# main.net
KiCad netlist of a schematic drawn in Altium Designer
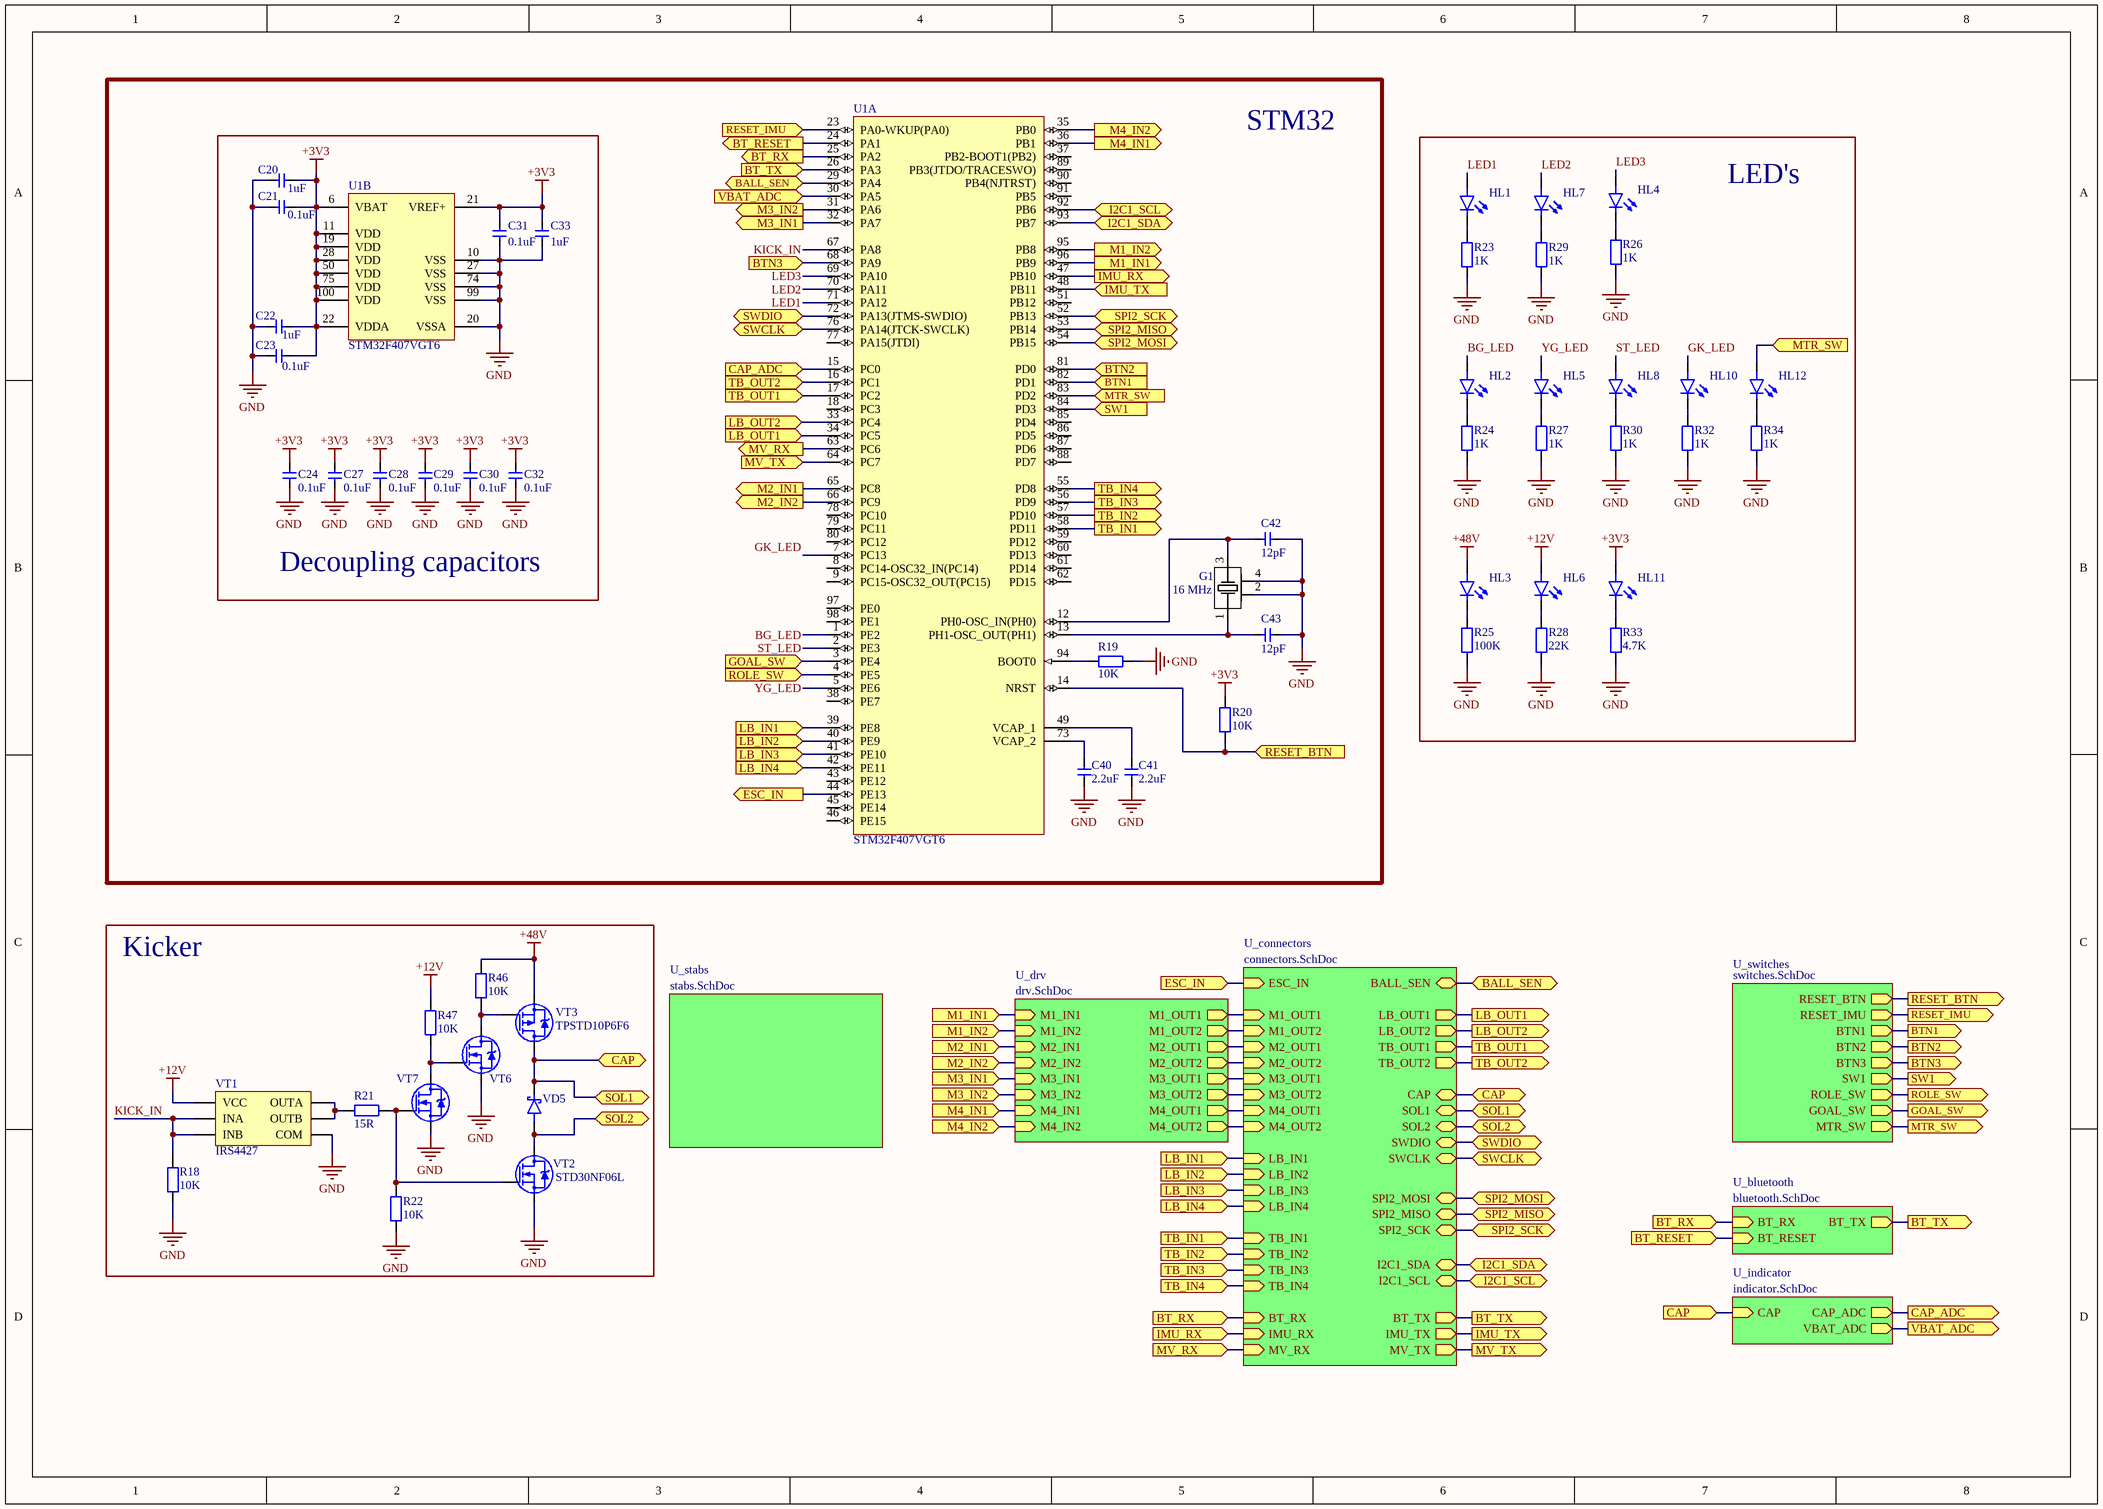
[diagram p0: main.SchDoc]

(export (version "E")
  (design (tool "Eeschema 10.0.6"))
  (components
    (comp (ref "C20")
      (value "1uF")
      (footprint "CAP0805")
      (description "Ceramic SMD Cap")
      (libsource (lib "Asterisk") (part "CAP Ceramic"))
    )
    (comp (ref "C21")
      (value "0.1uF")
      (footprint "CAP0805")
      (description "Ceramic SMD Cap")
      (libsource (lib "Asterisk") (part "CAP Ceramic"))
    )
    (comp (ref "C22")
      (value "1uF")
      (footprint "CAP0805")
      (description "Ceramic SMD Cap")
      (libsource (lib "Asterisk") (part "CAP Ceramic"))
    )
    (comp (ref "C23")
      (value "0.1uF")
      (footprint "CAP0805")
      (description "Ceramic SMD Cap")
      (libsource (lib "Asterisk") (part "CAP Ceramic"))
    )
    (comp (ref "C24")
      (value "0.1uF")
      (footprint "CAP0805")
      (description "Ceramic SMD Cap")
      (libsource (lib "Asterisk") (part "CAP Ceramic"))
    )
    (comp (ref "C27")
      (value "0.1uF")
      (footprint "CAP0805")
      (description "Ceramic SMD Cap")
      (libsource (lib "Asterisk") (part "CAP Ceramic"))
    )
    (comp (ref "C28")
      (value "0.1uF")
      (footprint "CAP0805")
      (description "Ceramic SMD Cap")
      (libsource (lib "Asterisk") (part "CAP Ceramic"))
    )
    (comp (ref "C29")
      (value "0.1uF")
      (footprint "CAP0805")
      (description "Ceramic SMD Cap")
      (libsource (lib "Asterisk") (part "CAP Ceramic"))
    )
    (comp (ref "C30")
      (value "0.1uF")
      (footprint "CAP0805")
      (description "Ceramic SMD Cap")
      (libsource (lib "Asterisk") (part "CAP Ceramic"))
    )
    (comp (ref "C31")
      (value "0.1uF")
      (footprint "CAP0805")
      (description "Ceramic SMD Cap")
      (libsource (lib "Asterisk") (part "CAP Ceramic"))
    )
    (comp (ref "C32")
      (value "0.1uF")
      (footprint "CAP0805")
      (description "Ceramic SMD Cap")
      (libsource (lib "Asterisk") (part "CAP Ceramic"))
    )
    (comp (ref "C33")
      (value "1uF")
      (footprint "CAP0805")
      (description "Ceramic SMD Cap")
      (libsource (lib "Asterisk") (part "CAP Ceramic"))
    )
    (comp (ref "C40")
      (value "2.2uF")
      (footprint "CAP0805")
      (description "Ceramic SMD Cap")
      (libsource (lib "") (part "CAP Ceramic_1"))
    )
    (comp (ref "C41")
      (value "2.2uF")
      (footprint "CAP0805")
      (description "Ceramic SMD Cap")
      (libsource (lib "") (part "CAP Ceramic_1"))
    )
    (comp (ref "C42")
      (value "12pF")
      (footprint "CAP0805")
      (description "Ceramic SMD Cap")
      (libsource (lib "Asterisk") (part "CAP Ceramic"))
    )
    (comp (ref "C43")
      (value "12pF")
      (footprint "CAP0805")
      (description "Ceramic SMD Cap")
      (libsource (lib "Asterisk") (part "CAP Ceramic"))
    )
    (comp (ref "G1")
      (value "16 MHz")
      (footprint "TSX-3225")
      (description "quartz 16MHz")
      (fields
        (field (name "PART NUMBER") "TSX-3225 24.0000MF15X-AC6")
        (field (name "DIGI-KEY PART NUMBER") "SER4180CT-ND")
      )
      (libsource (lib "SssAccesDatbase") (part "CTX957CT"))
    )
    (comp (ref "HL1")
      (value "White")
      (footprint "LED0603_WHITE")
      (description "LED1")
      (libsource (lib "Asterisk") (part "LED"))
    )
    (comp (ref "HL2")
      (value "White")
      (footprint "LED0603_WHITE")
      (description "BG")
      (libsource (lib "Asterisk") (part "LED"))
    )
    (comp (ref "HL3")
      (value "Green")
      (footprint "LED0603_GREEN")
      (description "48V power")
      (libsource (lib "Asterisk") (part "LED"))
    )
    (comp (ref "HL4")
      (value "White")
      (footprint "LED0603_WHITE")
      (description "LED3")
      (libsource (lib "Asterisk") (part "LED"))
    )
    (comp (ref "HL5")
      (value "White")
      (footprint "LED0603_WHITE")
      (description "YG")
      (libsource (lib "Asterisk") (part "LED"))
    )
    (comp (ref "HL6")
      (value "Green")
      (footprint "LED0603_GREEN")
      (description "12V power")
      (libsource (lib "Asterisk") (part "LED"))
    )
    (comp (ref "HL7")
      (value "White")
      (footprint "LED0603_WHITE")
      (description "LED2")
      (libsource (lib "Asterisk") (part "LED"))
    )
    (comp (ref "HL8")
      (value "White")
      (footprint "LED0603_WHITE")
      (description "ST")
      (libsource (lib "Asterisk") (part "LED"))
    )
    (comp (ref "HL10")
      (value "White")
      (footprint "LED0603_WHITE")
      (description "GK")
      (libsource (lib "Asterisk") (part "LED"))
    )
    (comp (ref "HL11")
      (value "Green")
      (footprint "LED0603_GREEN")
      (description "3V3 power")
      (libsource (lib "Asterisk") (part "LED"))
    )
    (comp (ref "HL12")
      (value "Red")
      (footprint "LED0603_RED")
      (description "M_ON")
      (libsource (lib "Asterisk") (part "LED"))
    )
    (comp (ref "R18")
      (value "10K")
      (footprint "RES0805")
      (description "RES smd")
      (libsource (lib "Asterisk") (part "RES"))
    )
    (comp (ref "R19")
      (value "10K")
      (footprint "RES0805")
      (description "RES smd")
      (libsource (lib "Asterisk") (part "RES"))
    )
    (comp (ref "R20")
      (value "10K")
      (footprint "RES0805")
      (description "RES smd")
      (libsource (lib "Asterisk") (part "RES"))
    )
    (comp (ref "R21")
      (value "15R")
      (footprint "RES1206")
      (description "RES smd")
      (libsource (lib "Asterisk") (part "RES"))
    )
    (comp (ref "R22")
      (value "10K")
      (footprint "RES0805")
      (description "RES smd")
      (libsource (lib "Asterisk") (part "RES"))
    )
    (comp (ref "R23")
      (value "1K")
      (footprint "RES0805")
      (description "RES smd")
      (libsource (lib "Asterisk") (part "RES"))
    )
    (comp (ref "R24")
      (value "1K")
      (footprint "RES0805")
      (description "RES smd")
      (libsource (lib "Asterisk") (part "RES"))
    )
    (comp (ref "R25")
      (value "100K")
      (footprint "RES0805")
      (description "RES smd")
      (libsource (lib "Asterisk") (part "RES"))
    )
    (comp (ref "R26")
      (value "1K")
      (footprint "RES0805")
      (description "RES smd")
      (libsource (lib "Asterisk") (part "RES"))
    )
    (comp (ref "R27")
      (value "1K")
      (footprint "RES0805")
      (description "RES smd")
      (libsource (lib "Asterisk") (part "RES"))
    )
    (comp (ref "R28")
      (value "22K")
      (footprint "RES0805")
      (description "RES smd")
      (libsource (lib "Asterisk") (part "RES"))
    )
    (comp (ref "R29")
      (value "1K")
      (footprint "RES0805")
      (description "RES smd")
      (libsource (lib "Asterisk") (part "RES"))
    )
    (comp (ref "R30")
      (value "1K")
      (footprint "RES0805")
      (description "RES smd")
      (libsource (lib "Asterisk") (part "RES"))
    )
    (comp (ref "R32")
      (value "1K")
      (footprint "RES0805")
      (description "RES smd")
      (libsource (lib "Asterisk") (part "RES"))
    )
    (comp (ref "R33")
      (value "4.7K")
      (footprint "RES0805")
      (description "RES smd")
      (libsource (lib "Asterisk") (part "RES"))
    )
    (comp (ref "R34")
      (value "1K")
      (footprint "RES0805")
      (description "RES smd")
      (libsource (lib "Asterisk") (part "RES"))
    )
    (comp (ref "R46")
      (value "10K")
      (footprint "RES0805")
      (description "RES smd")
      (libsource (lib "Asterisk") (part "RES"))
    )
    (comp (ref "R47")
      (value "10K")
      (footprint "RES0805")
      (description "RES smd")
      (libsource (lib "Asterisk") (part "RES"))
    )
    (comp (ref "U1")
      (value "STM32F407VGT6")
      (footprint "LQFP100")
      (fields (field (name "MANUFACTURER") "STMicroelectronics"))
      (libsource (lib "") (part "STM32F407VGT6_1"))
    )
    (comp (ref "VD5")
      (value "~")
      (footprint "DO-214AC (SMA)")
      (description "Diode Schottky")
      (libsource (lib "Asterisk") (part "Diode Schottky"))
    )
    (comp (ref "VT1")
      (value "IRS4427")
      (footprint "SOIC-8")
      (description "Mosfet driver")
      (libsource (lib "Asterisk") (part "IRS4427"))
    )
    (comp (ref "VT2")
      (value "STD30NF06L")
      (footprint "DPAK")
      (description "N-MOSFET\r\nUds = 60 V\r\nIds = 30 A\r\nRds = 0.023 Ohm\r\nP = 55 W")
      (libsource (lib "Asterisk") (part "STD30NF06L"))
    )
    (comp (ref "VT3")
      (value "TPSTD10P6F6")
      (footprint "DPAK")
      (description "P-MOSFET\r\nUds = 60 V\r\nIds = 13 A\r\nRds = 0.100 Ohm\r\nP = 60 W")
      (libsource (lib "Asterisk") (part "TPSTD10P6F6"))
    )
    (comp (ref "VT6")
      (value "IRLML2502")
      (footprint "SOT-23-3")
      (description "N-MOSFET\r\nUds = 20 V\r\nIds = 4.2 A\r\nRds = 0.035 Ohm\r\nP = 1,25 W")
      (libsource (lib "Asterisk") (part "IRLML2502"))
    )
    (comp (ref "VT7")
      (value "IRLML2502")
      (footprint "SOT-23-3")
      (description "N-MOSFET\r\nUds = 20 V\r\nIds = 4.2 A\r\nRds = 0.035 Ohm\r\nP = 8 W")
      (libsource (lib "Asterisk") (part "IRLML2502"))
    )
  )
  (nets
    (net (code "1") (name "+3V3") (class "Default")
      (node (ref "C20") (pin "1") (pinfunction "1_1") (pintype "passive"))
      (node (ref "C21") (pin "1") (pinfunction "1_1") (pintype "passive"))
      (node (ref "C22") (pin "1") (pinfunction "1_1") (pintype "passive"))
      (node (ref "C23") (pin "1") (pinfunction "1_1") (pintype "passive"))
      (node (ref "C24") (pin "1") (pinfunction "1_1") (pintype "passive"))
      (node (ref "C27") (pin "1") (pinfunction "1_1") (pintype "passive"))
      (node (ref "C28") (pin "1") (pinfunction "1_1") (pintype "passive"))
      (node (ref "C29") (pin "1") (pinfunction "1_1") (pintype "passive"))
      (node (ref "C30") (pin "1") (pinfunction "1_1") (pintype "passive"))
      (node (ref "C31") (pin "2") (pinfunction "2_2") (pintype "passive"))
      (node (ref "C32") (pin "1") (pinfunction "1_1") (pintype "passive"))
      (node (ref "C33") (pin "2") (pinfunction "2_2") (pintype "passive"))
      (node (ref "HL11") (pin "2") (pinfunction "A_2") (pintype "passive"))
      (node (ref "R20") (pin "1") (pinfunction "1_1") (pintype "passive"))
      (node (ref "U1") (pin "100") (pinfunction "VDD_100") (pintype "power_in"))
      (node (ref "U1") (pin "11") (pinfunction "VDD_11") (pintype "power_in"))
      (node (ref "U1") (pin "19") (pinfunction "VDD_19") (pintype "power_in"))
      (node (ref "U1") (pin "21") (pinfunction "VREF+_21") (pintype "power_in"))
      (node (ref "U1") (pin "22") (pinfunction "VDDA_22") (pintype "power_in"))
      (node (ref "U1") (pin "28") (pinfunction "VDD_28") (pintype "power_in"))
      (node (ref "U1") (pin "50") (pinfunction "VDD_50") (pintype "power_in"))
      (node (ref "U1") (pin "6") (pinfunction "VBAT_6") (pintype "power_in"))
      (node (ref "U1") (pin "75") (pinfunction "VDD_75") (pintype "power_in"))
    )
    (net (code "2") (name "+12V") (class "Default")
      (node (ref "HL6") (pin "2") (pinfunction "A_2") (pintype "passive"))
      (node (ref "R47") (pin "2") (pinfunction "2_2") (pintype "passive"))
      (node (ref "VT1") (pin "6") (pinfunction "VCC_6") (pintype "passive"))
    )
    (net (code "3") (name "+48V") (class "Default")
      (node (ref "HL3") (pin "2") (pinfunction "A_2") (pintype "passive"))
      (node (ref "R46") (pin "2") (pinfunction "2_2") (pintype "passive"))
      (node (ref "VT3") (pin "S") (pinfunction "S_S") (pintype "passive"))
    )
    (net (code "4") (name "/BALL_SEN") (class "Default")
      (node (ref "U1") (pin "29") (pinfunction "PA4_29") (pintype "bidirectional"))
    )
    (net (code "5") (name "/BG_LED") (class "Default")
      (node (ref "HL2") (pin "2") (pinfunction "A_2") (pintype "passive"))
      (node (ref "U1") (pin "1") (pinfunction "PE2_1") (pintype "bidirectional"))
    )
    (net (code "6") (name "/BTN1") (class "Default")
      (node (ref "U1") (pin "82") (pinfunction "PD1_82") (pintype "bidirectional"))
    )
    (net (code "7") (name "/BTN2") (class "Default")
      (node (ref "U1") (pin "81") (pinfunction "PD0_81") (pintype "bidirectional"))
    )
    (net (code "8") (name "/BTN3") (class "Default")
      (node (ref "U1") (pin "68") (pinfunction "PA9_68") (pintype "bidirectional"))
    )
    (net (code "9") (name "/BT_RESET") (class "Default")
      (node (ref "U1") (pin "24") (pinfunction "PA1_24") (pintype "bidirectional"))
    )
    (net (code "10") (name "/BT_RX") (class "Default")
      (node (ref "U1") (pin "25") (pinfunction "PA2_25") (pintype "bidirectional"))
    )
    (net (code "11") (name "/BT_TX") (class "Default")
      (node (ref "U1") (pin "26") (pinfunction "PA3_26") (pintype "bidirectional"))
    )
    (net (code "12") (name "/CAP") (class "Default")
      (node (ref "VD5") (pin "K") (pinfunction "K_K") (pintype "passive"))
      (node (ref "VT3") (pin "D") (pinfunction "D_D") (pintype "passive"))
    )
    (net (code "13") (name "/CAP_ADC") (class "Default")
      (node (ref "U1") (pin "15") (pinfunction "PC0_15") (pintype "bidirectional"))
    )
    (net (code "14") (name "/ESC_IN") (class "Default")
      (node (ref "U1") (pin "44") (pinfunction "PE13_44") (pintype "bidirectional"))
    )
    (net (code "15") (name "/GK_LED") (class "Default")
      (node (ref "HL10") (pin "2") (pinfunction "A_2") (pintype "passive"))
      (node (ref "U1") (pin "7") (pinfunction "PC13_7") (pintype "bidirectional"))
    )
    (net (code "16") (name "/GOAL_SW") (class "Default")
      (node (ref "U1") (pin "3") (pinfunction "PE4_3") (pintype "bidirectional"))
    )
    (net (code "17") (name "/I2C1_SCL") (class "Default")
      (node (ref "U1") (pin "92") (pinfunction "PB6_92") (pintype "bidirectional"))
    )
    (net (code "18") (name "/I2C1_SDA") (class "Default")
      (node (ref "U1") (pin "93") (pinfunction "PB7_93") (pintype "bidirectional"))
    )
    (net (code "19") (name "/IMU_RX") (class "Default")
      (node (ref "U1") (pin "47") (pinfunction "PB10_47") (pintype "bidirectional"))
    )
    (net (code "20") (name "/IMU_TX") (class "Default")
      (node (ref "U1") (pin "48") (pinfunction "PB11_48") (pintype "bidirectional"))
    )
    (net (code "21") (name "/KICK_IN") (class "Default")
      (node (ref "R18") (pin "2") (pinfunction "2_2") (pintype "passive"))
      (node (ref "U1") (pin "67") (pinfunction "PA8_67") (pintype "bidirectional"))
      (node (ref "VT1") (pin "2") (pinfunction "INA_2") (pintype "passive"))
      (node (ref "VT1") (pin "4") (pinfunction "INB_4") (pintype "passive"))
    )
    (net (code "22") (name "/LB_IN1") (class "Default")
      (node (ref "U1") (pin "39") (pinfunction "PE8_39") (pintype "bidirectional"))
    )
    (net (code "23") (name "/LB_IN2") (class "Default")
      (node (ref "U1") (pin "40") (pinfunction "PE9_40") (pintype "bidirectional"))
    )
    (net (code "24") (name "/LB_IN3") (class "Default")
      (node (ref "U1") (pin "41") (pinfunction "PE10_41") (pintype "bidirectional"))
    )
    (net (code "25") (name "/LB_IN4") (class "Default")
      (node (ref "U1") (pin "42") (pinfunction "PE11_42") (pintype "bidirectional"))
    )
    (net (code "26") (name "/LB_OUT1") (class "Default")
      (node (ref "U1") (pin "34") (pinfunction "PC5_34") (pintype "bidirectional"))
    )
    (net (code "27") (name "/LB_OUT2") (class "Default")
      (node (ref "U1") (pin "33") (pinfunction "PC4_33") (pintype "bidirectional"))
    )
    (net (code "28") (name "/LED1") (class "Default")
      (node (ref "HL1") (pin "2") (pinfunction "A_2") (pintype "passive"))
      (node (ref "U1") (pin "71") (pinfunction "PA12_71") (pintype "bidirectional"))
    )
    (net (code "29") (name "/LED2") (class "Default")
      (node (ref "HL7") (pin "2") (pinfunction "A_2") (pintype "passive"))
      (node (ref "U1") (pin "70") (pinfunction "PA11_70") (pintype "bidirectional"))
    )
    (net (code "30") (name "/LED3") (class "Default")
      (node (ref "HL4") (pin "2") (pinfunction "A_2") (pintype "passive"))
      (node (ref "U1") (pin "69") (pinfunction "PA10_69") (pintype "bidirectional"))
    )
    (net (code "31") (name "/M1_IN1") (class "Default")
      (node (ref "U1") (pin "96") (pinfunction "PB9_96") (pintype "bidirectional"))
    )
    (net (code "32") (name "/M1_IN2") (class "Default")
      (node (ref "U1") (pin "95") (pinfunction "PB8_95") (pintype "bidirectional"))
    )
    (net (code "35") (name "/M2_IN1") (class "Default")
      (node (ref "U1") (pin "65") (pinfunction "PC8_65") (pintype "bidirectional"))
    )
    (net (code "36") (name "/M2_IN2") (class "Default")
      (node (ref "U1") (pin "66") (pinfunction "PC9_66") (pintype "bidirectional"))
    )
    (net (code "39") (name "/M3_IN1") (class "Default")
      (node (ref "U1") (pin "32") (pinfunction "PA7_32") (pintype "bidirectional"))
    )
    (net (code "40") (name "/M3_IN2") (class "Default")
      (node (ref "U1") (pin "31") (pinfunction "PA6_31") (pintype "bidirectional"))
    )
    (net (code "43") (name "/M4_IN1") (class "Default")
      (node (ref "U1") (pin "36") (pinfunction "PB1_36") (pintype "bidirectional"))
    )
    (net (code "44") (name "/M4_IN2") (class "Default")
      (node (ref "U1") (pin "35") (pinfunction "PB0_35") (pintype "bidirectional"))
    )
    (net (code "47") (name "/MTR_SW") (class "Default")
      (node (ref "HL12") (pin "2") (pinfunction "A_2") (pintype "passive"))
      (node (ref "U1") (pin "83") (pinfunction "PD2_83") (pintype "bidirectional"))
    )
    (net (code "48") (name "/MV_RX") (class "Default")
      (node (ref "U1") (pin "63") (pinfunction "PC6_63") (pintype "bidirectional"))
    )
    (net (code "49") (name "/MV_TX") (class "Default")
      (node (ref "U1") (pin "64") (pinfunction "PC7_64") (pintype "bidirectional"))
    )
    (net (code "50") (name "/RESET_BTN") (class "Default")
      (node (ref "R20") (pin "2") (pinfunction "2_2") (pintype "passive"))
      (node (ref "U1") (pin "14") (pinfunction "NRST_14") (pintype "bidirectional"))
    )
    (net (code "51") (name "/RESET_IMU") (class "Default")
      (node (ref "U1") (pin "23") (pinfunction "PA0-WKUP(PA0)_23") (pintype "bidirectional"))
    )
    (net (code "52") (name "/ROLE_SW") (class "Default")
      (node (ref "U1") (pin "4") (pinfunction "PE5_4") (pintype "bidirectional"))
    )
    (net (code "53") (name "/SOL2") (class "Default")
      (node (ref "VD5") (pin "A") (pinfunction "A_A") (pintype "passive"))
      (node (ref "VT2") (pin "D") (pinfunction "D_D") (pintype "passive"))
    )
    (net (code "54") (name "/SPI2_MISO") (class "Default")
      (node (ref "U1") (pin "53") (pinfunction "PB14_53") (pintype "bidirectional"))
    )
    (net (code "55") (name "/SPI2_MOSI") (class "Default")
      (node (ref "U1") (pin "54") (pinfunction "PB15_54") (pintype "bidirectional"))
    )
    (net (code "56") (name "/SPI2_SCK") (class "Default")
      (node (ref "U1") (pin "52") (pinfunction "PB13_52") (pintype "bidirectional"))
    )
    (net (code "57") (name "/ST_LED") (class "Default")
      (node (ref "HL8") (pin "2") (pinfunction "A_2") (pintype "passive"))
      (node (ref "U1") (pin "2") (pinfunction "PE3_2") (pintype "bidirectional"))
    )
    (net (code "58") (name "/SW1") (class "Default")
      (node (ref "U1") (pin "84") (pinfunction "PD3_84") (pintype "bidirectional"))
    )
    (net (code "59") (name "/SWCLK") (class "Default")
      (node (ref "U1") (pin "76") (pinfunction "PA14(JTCK-SWCLK)_76") (pintype "bidirectional"))
    )
    (net (code "60") (name "/SWDIO") (class "Default")
      (node (ref "U1") (pin "72") (pinfunction "PA13(JTMS-SWDIO)_72") (pintype "bidirectional"))
    )
    (net (code "61") (name "/TB_IN1") (class "Default")
      (node (ref "U1") (pin "58") (pinfunction "PD11_58") (pintype "bidirectional"))
    )
    (net (code "62") (name "/TB_IN2") (class "Default")
      (node (ref "U1") (pin "57") (pinfunction "PD10_57") (pintype "bidirectional"))
    )
    (net (code "63") (name "/TB_IN3") (class "Default")
      (node (ref "U1") (pin "56") (pinfunction "PD9_56") (pintype "bidirectional"))
    )
    (net (code "64") (name "/TB_IN4") (class "Default")
      (node (ref "U1") (pin "55") (pinfunction "PD8_55") (pintype "bidirectional"))
    )
    (net (code "65") (name "/TB_OUT1") (class "Default")
      (node (ref "U1") (pin "17") (pinfunction "PC2_17") (pintype "bidirectional"))
    )
    (net (code "66") (name "/TB_OUT2") (class "Default")
      (node (ref "U1") (pin "16") (pinfunction "PC1_16") (pintype "bidirectional"))
    )
    (net (code "67") (name "/VBAT_ADC") (class "Default")
      (node (ref "U1") (pin "30") (pinfunction "PA5_30") (pintype "bidirectional"))
    )
    (net (code "68") (name "/YG_LED") (class "Default")
      (node (ref "HL5") (pin "2") (pinfunction "A_2") (pintype "passive"))
      (node (ref "U1") (pin "5") (pinfunction "PE6_5") (pintype "bidirectional"))
    )
    (net (code "69") (name "GND") (class "Default")
      (node (ref "C20") (pin "2") (pinfunction "2_2") (pintype "passive"))
      (node (ref "C21") (pin "2") (pinfunction "2_2") (pintype "passive"))
      (node (ref "C22") (pin "2") (pinfunction "2_2") (pintype "passive"))
      (node (ref "C23") (pin "2") (pinfunction "2_2") (pintype "passive"))
      (node (ref "C24") (pin "2") (pinfunction "2_2") (pintype "passive"))
      (node (ref "C27") (pin "2") (pinfunction "2_2") (pintype "passive"))
      (node (ref "C28") (pin "2") (pinfunction "2_2") (pintype "passive"))
      (node (ref "C29") (pin "2") (pinfunction "2_2") (pintype "passive"))
      (node (ref "C30") (pin "2") (pinfunction "2_2") (pintype "passive"))
      (node (ref "C31") (pin "1") (pinfunction "1_1") (pintype "passive"))
      (node (ref "C32") (pin "2") (pinfunction "2_2") (pintype "passive"))
      (node (ref "C33") (pin "1") (pinfunction "1_1") (pintype "passive"))
      (node (ref "C40") (pin "1") (pinfunction "1_1") (pintype "passive"))
      (node (ref "C41") (pin "1") (pinfunction "1_1") (pintype "passive"))
      (node (ref "C42") (pin "2") (pinfunction "2_2") (pintype "passive"))
      (node (ref "C43") (pin "2") (pinfunction "2_2") (pintype "passive"))
      (node (ref "G1") (pin "2") (pinfunction "2_2") (pintype "passive"))
      (node (ref "G1") (pin "4") (pinfunction "4_4") (pintype "passive"))
      (node (ref "R18") (pin "1") (pinfunction "1_1") (pintype "passive"))
      (node (ref "R19") (pin "1") (pinfunction "1_1") (pintype "passive"))
      (node (ref "R22") (pin "1") (pinfunction "1_1") (pintype "passive"))
      (node (ref "R23") (pin "1") (pinfunction "1_1") (pintype "passive"))
      (node (ref "R24") (pin "1") (pinfunction "1_1") (pintype "passive"))
      (node (ref "R25") (pin "1") (pinfunction "1_1") (pintype "passive"))
      (node (ref "R26") (pin "1") (pinfunction "1_1") (pintype "passive"))
      (node (ref "R27") (pin "1") (pinfunction "1_1") (pintype "passive"))
      (node (ref "R28") (pin "1") (pinfunction "1_1") (pintype "passive"))
      (node (ref "R29") (pin "1") (pinfunction "1_1") (pintype "passive"))
      (node (ref "R30") (pin "1") (pinfunction "1_1") (pintype "passive"))
      (node (ref "R32") (pin "1") (pinfunction "1_1") (pintype "passive"))
      (node (ref "R33") (pin "1") (pinfunction "1_1") (pintype "passive"))
      (node (ref "R34") (pin "1") (pinfunction "1_1") (pintype "passive"))
      (node (ref "U1") (pin "10") (pinfunction "VSS_10") (pintype "power_in"))
      (node (ref "U1") (pin "20") (pinfunction "VSSA_20") (pintype "power_in"))
      (node (ref "U1") (pin "27") (pinfunction "VSS_27") (pintype "power_in"))
      (node (ref "U1") (pin "74") (pinfunction "VSS_74") (pintype "power_in"))
      (node (ref "U1") (pin "99") (pinfunction "VSS_99") (pintype "power_in"))
      (node (ref "VT1") (pin "3") (pinfunction "COM_3") (pintype "passive"))
      (node (ref "VT2") (pin "S") (pinfunction "S_S") (pintype "passive"))
      (node (ref "VT6") (pin "S") (pinfunction "S_S") (pintype "passive"))
      (node (ref "VT7") (pin "S") (pinfunction "S_S") (pintype "passive"))
    )
    (net (code "70") (name "Net-(HL1-K)") (class "Default")
      (node (ref "HL1") (pin "1") (pinfunction "K_1") (pintype "passive"))
      (node (ref "R23") (pin "2") (pinfunction "2_2") (pintype "passive"))
    )
    (net (code "71") (name "Net-(HL2-K)") (class "Default")
      (node (ref "HL2") (pin "1") (pinfunction "K_1") (pintype "passive"))
      (node (ref "R24") (pin "2") (pinfunction "2_2") (pintype "passive"))
    )
    (net (code "72") (name "Net-(HL3-K)") (class "Default")
      (node (ref "HL3") (pin "1") (pinfunction "K_1") (pintype "passive"))
      (node (ref "R25") (pin "2") (pinfunction "2_2") (pintype "passive"))
    )
    (net (code "73") (name "Net-(HL4-K)") (class "Default")
      (node (ref "HL4") (pin "1") (pinfunction "K_1") (pintype "passive"))
      (node (ref "R26") (pin "2") (pinfunction "2_2") (pintype "passive"))
    )
    (net (code "74") (name "Net-(HL5-K)") (class "Default")
      (node (ref "HL5") (pin "1") (pinfunction "K_1") (pintype "passive"))
      (node (ref "R27") (pin "2") (pinfunction "2_2") (pintype "passive"))
    )
    (net (code "75") (name "Net-(HL6-K)") (class "Default")
      (node (ref "HL6") (pin "1") (pinfunction "K_1") (pintype "passive"))
      (node (ref "R28") (pin "2") (pinfunction "2_2") (pintype "passive"))
    )
    (net (code "76") (name "Net-(HL7-K)") (class "Default")
      (node (ref "HL7") (pin "1") (pinfunction "K_1") (pintype "passive"))
      (node (ref "R29") (pin "2") (pinfunction "2_2") (pintype "passive"))
    )
    (net (code "77") (name "Net-(HL8-K)") (class "Default")
      (node (ref "HL8") (pin "1") (pinfunction "K_1") (pintype "passive"))
      (node (ref "R30") (pin "2") (pinfunction "2_2") (pintype "passive"))
    )
    (net (code "78") (name "Net-(HL10-K)") (class "Default")
      (node (ref "HL10") (pin "1") (pinfunction "K_1") (pintype "passive"))
      (node (ref "R32") (pin "2") (pinfunction "2_2") (pintype "passive"))
    )
    (net (code "79") (name "Net-(HL11-K)") (class "Default")
      (node (ref "HL11") (pin "1") (pinfunction "K_1") (pintype "passive"))
      (node (ref "R33") (pin "2") (pinfunction "2_2") (pintype "passive"))
    )
    (net (code "80") (name "Net-(HL12-K)") (class "Default")
      (node (ref "HL12") (pin "1") (pinfunction "K_1") (pintype "passive"))
      (node (ref "R34") (pin "2") (pinfunction "2_2") (pintype "passive"))
    )
    (net (code "81") (name "Net-(R21-Pad2)") (class "Default")
      (node (ref "R21") (pin "2") (pinfunction "2_2") (pintype "passive"))
      (node (ref "R22") (pin "2") (pinfunction "2_2") (pintype "passive"))
      (node (ref "VT2") (pin "G") (pinfunction "G_G") (pintype "passive"))
      (node (ref "VT7") (pin "G") (pinfunction "G_G") (pintype "passive"))
    )
    (net (code "82") (name "Net-(R46-Pad1)") (class "Default")
      (node (ref "R46") (pin "1") (pinfunction "1_1") (pintype "passive"))
      (node (ref "VT3") (pin "G") (pinfunction "G_G") (pintype "passive"))
      (node (ref "VT6") (pin "D") (pinfunction "D_D") (pintype "passive"))
    )
    (net (code "83") (name "Net-(R47-Pad1)") (class "Default")
      (node (ref "R47") (pin "1") (pinfunction "1_1") (pintype "passive"))
      (node (ref "VT6") (pin "G") (pinfunction "G_G") (pintype "passive"))
      (node (ref "VT7") (pin "D") (pinfunction "D_D") (pintype "passive"))
    )
    (net (code "84") (name "Net-(U1A-BOOT0)") (class "Default")
      (node (ref "R19") (pin "2") (pinfunction "2_2") (pintype "passive"))
      (node (ref "U1") (pin "94") (pinfunction "BOOT0_94") (pintype "input"))
    )
    (net (code "85") (name "Net-(U1A-PH0-OSC_IN(PH0))") (class "Default")
      (node (ref "C42") (pin "1") (pinfunction "1_1") (pintype "passive"))
      (node (ref "G1") (pin "3") (pinfunction "3_3") (pintype "passive"))
      (node (ref "U1") (pin "12") (pinfunction "PH0-OSC_IN(PH0)_12") (pintype "bidirectional"))
    )
    (net (code "86") (name "Net-(U1A-PH1-OSC_OUT(PH1))") (class "Default")
      (node (ref "C43") (pin "1") (pinfunction "1_1") (pintype "passive"))
      (node (ref "G1") (pin "1") (pinfunction "1_1") (pintype "passive"))
      (node (ref "U1") (pin "13") (pinfunction "PH1-OSC_OUT(PH1)_13") (pintype "bidirectional"))
    )
    (net (code "87") (name "Net-(U1A-VCAP_1)") (class "Default")
      (node (ref "C41") (pin "2") (pinfunction "2_2") (pintype "passive"))
      (node (ref "U1") (pin "49") (pinfunction "VCAP_1_49") (pintype "power_in"))
    )
    (net (code "88") (name "Net-(U1A-VCAP_2)") (class "Default")
      (node (ref "C40") (pin "2") (pinfunction "2_2") (pintype "passive"))
      (node (ref "U1") (pin "73") (pinfunction "VCAP_2_73") (pintype "power_in"))
    )
    (net (code "89") (name "Net-(VT1-OUTA)") (class "Default")
      (node (ref "R21") (pin "1") (pinfunction "1_1") (pintype "passive"))
      (node (ref "VT1") (pin "5") (pinfunction "OUTB_5") (pintype "passive"))
      (node (ref "VT1") (pin "7") (pinfunction "OUTA_7") (pintype "passive"))
    )
    (net (code "90") (name "unconnected-(U1A-PA15(JTDI)-Pad77)") (class "Default")
      (node (ref "U1") (pin "77") (pinfunction "PA15(JTDI)_77") (pintype "bidirectional"))
    )
    (net (code "91") (name "unconnected-(U1A-PB2-BOOT1(PB2)-Pad37)") (class "Default")
      (node (ref "U1") (pin "37") (pinfunction "PB2-BOOT1(PB2)_37") (pintype "bidirectional"))
    )
    (net (code "92") (name "unconnected-(U1A-PB3(JTDO{slash}TRACESWO)-Pad89)") (class "Default")
      (node (ref "U1") (pin "89") (pinfunction "PB3(JTDO/TRACESWO)_89") (pintype "bidirectional"))
    )
    (net (code "93") (name "unconnected-(U1A-PB4(NJTRST)-Pad90)") (class "Default")
      (node (ref "U1") (pin "90") (pinfunction "PB4(NJTRST)_90") (pintype "bidirectional"))
    )
    (net (code "94") (name "unconnected-(U1A-PB5-Pad91)") (class "Default")
      (node (ref "U1") (pin "91") (pinfunction "PB5_91") (pintype "bidirectional"))
    )
    (net (code "95") (name "unconnected-(U1A-PB12-Pad51)") (class "Default")
      (node (ref "U1") (pin "51") (pinfunction "PB12_51") (pintype "bidirectional"))
    )
    (net (code "96") (name "unconnected-(U1A-PC3-Pad18)") (class "Default")
      (node (ref "U1") (pin "18") (pinfunction "PC3_18") (pintype "bidirectional"))
    )
    (net (code "97") (name "unconnected-(U1A-PC10-Pad78)") (class "Default")
      (node (ref "U1") (pin "78") (pinfunction "PC10_78") (pintype "bidirectional"))
    )
    (net (code "98") (name "unconnected-(U1A-PC11-Pad79)") (class "Default")
      (node (ref "U1") (pin "79") (pinfunction "PC11_79") (pintype "bidirectional"))
    )
    (net (code "99") (name "unconnected-(U1A-PC12-Pad80)") (class "Default")
      (node (ref "U1") (pin "80") (pinfunction "PC12_80") (pintype "bidirectional"))
    )
    (net (code "100") (name "unconnected-(U1A-PC14-OSC32_IN(PC14)-Pad8)") (class "Default")
      (node (ref "U1") (pin "8") (pinfunction "PC14-OSC32_IN(PC14)_8") (pintype "bidirectional"))
    )
    (net (code "101") (name "unconnected-(U1A-PC15-OSC32_OUT(PC15)-Pad9)") (class "Default")
      (node (ref "U1") (pin "9") (pinfunction "PC15-OSC32_OUT(PC15)_9") (pintype "bidirectional"))
    )
    (net (code "102") (name "unconnected-(U1A-PD4-Pad85)") (class "Default")
      (node (ref "U1") (pin "85") (pinfunction "PD4_85") (pintype "bidirectional"))
    )
    (net (code "103") (name "unconnected-(U1A-PD5-Pad86)") (class "Default")
      (node (ref "U1") (pin "86") (pinfunction "PD5_86") (pintype "bidirectional"))
    )
    (net (code "104") (name "unconnected-(U1A-PD6-Pad87)") (class "Default")
      (node (ref "U1") (pin "87") (pinfunction "PD6_87") (pintype "bidirectional"))
    )
    (net (code "105") (name "unconnected-(U1A-PD7-Pad88)") (class "Default")
      (node (ref "U1") (pin "88") (pinfunction "PD7_88") (pintype "bidirectional"))
    )
    (net (code "106") (name "unconnected-(U1A-PD12-Pad59)") (class "Default")
      (node (ref "U1") (pin "59") (pinfunction "PD12_59") (pintype "bidirectional"))
    )
    (net (code "107") (name "unconnected-(U1A-PD13-Pad60)") (class "Default")
      (node (ref "U1") (pin "60") (pinfunction "PD13_60") (pintype "bidirectional"))
    )
    (net (code "108") (name "unconnected-(U1A-PD14-Pad61)") (class "Default")
      (node (ref "U1") (pin "61") (pinfunction "PD14_61") (pintype "bidirectional"))
    )
    (net (code "109") (name "unconnected-(U1A-PD15-Pad62)") (class "Default")
      (node (ref "U1") (pin "62") (pinfunction "PD15_62") (pintype "bidirectional"))
    )
    (net (code "110") (name "unconnected-(U1A-PE0-Pad97)") (class "Default")
      (node (ref "U1") (pin "97") (pinfunction "PE0_97") (pintype "bidirectional"))
    )
    (net (code "111") (name "unconnected-(U1A-PE1-Pad98)") (class "Default")
      (node (ref "U1") (pin "98") (pinfunction "PE1_98") (pintype "bidirectional"))
    )
    (net (code "112") (name "unconnected-(U1A-PE7-Pad38)") (class "Default")
      (node (ref "U1") (pin "38") (pinfunction "PE7_38") (pintype "bidirectional"))
    )
    (net (code "113") (name "unconnected-(U1A-PE12-Pad43)") (class "Default")
      (node (ref "U1") (pin "43") (pinfunction "PE12_43") (pintype "bidirectional"))
    )
    (net (code "114") (name "unconnected-(U1A-PE14-Pad45)") (class "Default")
      (node (ref "U1") (pin "45") (pinfunction "PE14_45") (pintype "bidirectional"))
    )
    (net (code "115") (name "unconnected-(U1A-PE15-Pad46)") (class "Default")
      (node (ref "U1") (pin "46") (pinfunction "PE15_46") (pintype "bidirectional"))
    )
  )
)
